# MCU.net
KiCad netlist of a schematic drawn in Altium Designer
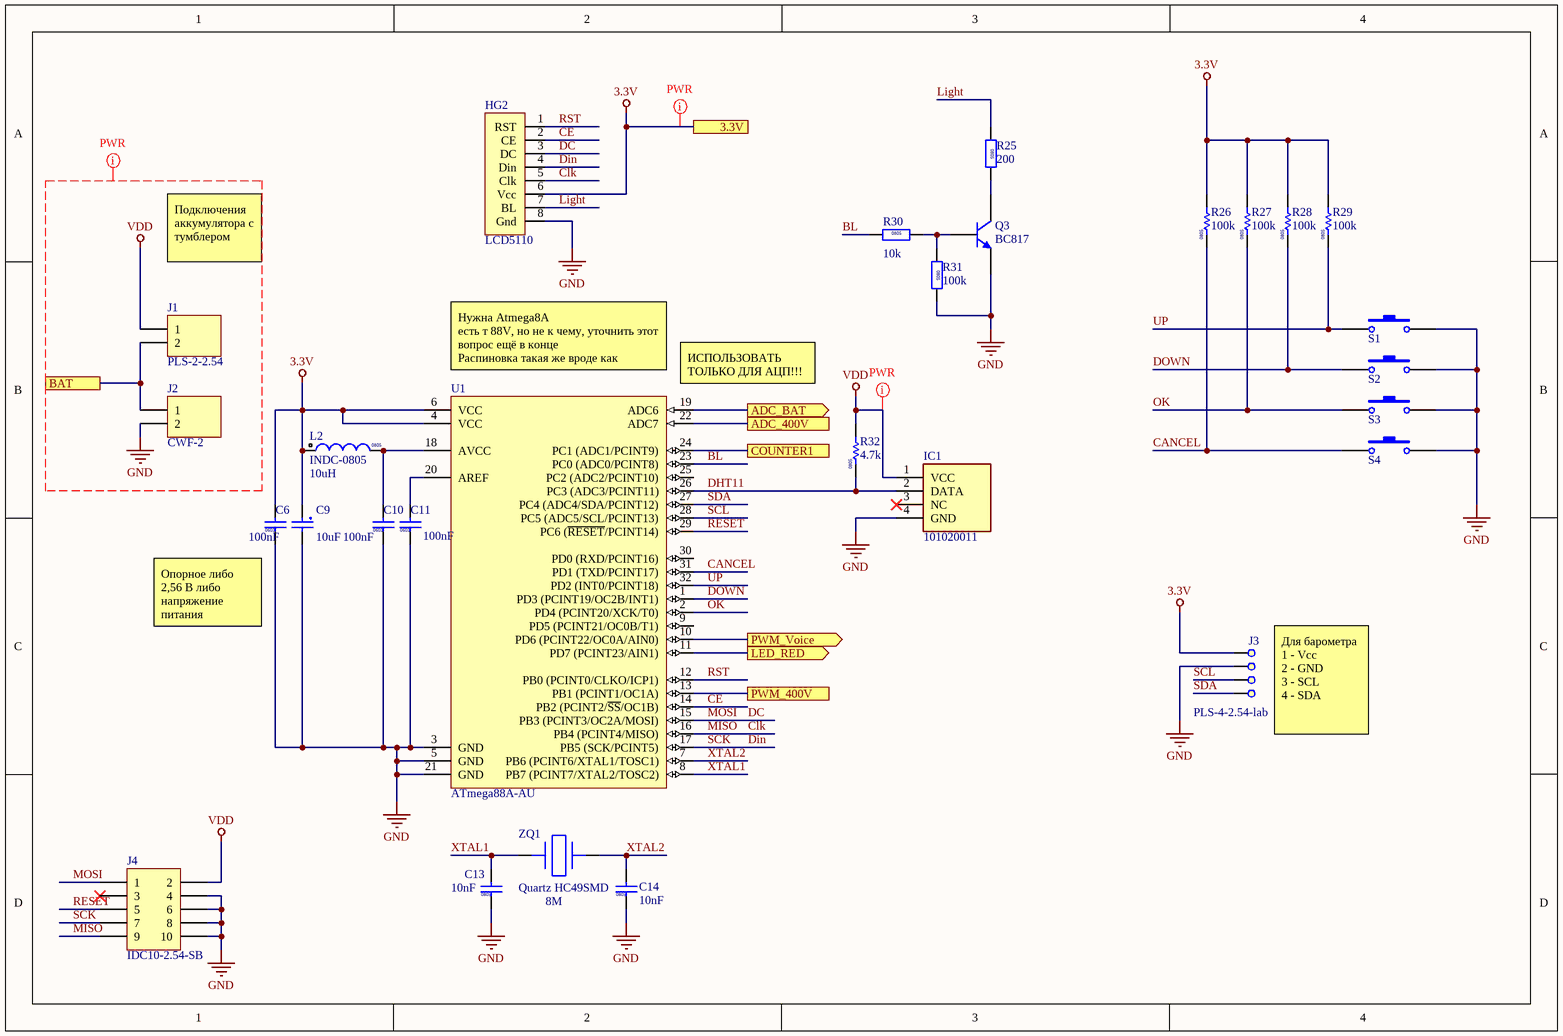
[diagram p0: MCU.SchDoc]

(export (version "E")
  (design (tool "Eeschema 10.0.6"))
  (components
    (comp (ref "C6")
      (value "100nF")
      (footprint "CAPC1608-0603L")
      (description "Capacitor 0603")
      (fields (field (name "Comment") "CAPC_0603"))
      (libsource (lib "Passive") (part "CAPC_0603"))
    )
    (comp (ref "C9")
      (value "10uF")
      (footprint "TCAPC_A")
      (description "Capacitor tantalum SMD type A")
      (fields (field (name "Comment") "TCAPC_A"))
      (libsource (lib "Passive") (part "TCAPC_A"))
    )
    (comp (ref "C10")
      (value "100nF")
      (footprint "CAPC1608-0603L")
      (description "Capacitor 0603")
      (fields (field (name "Comment") "CAPC_0603"))
      (libsource (lib "Passive") (part "CAPC_0603"))
    )
    (comp (ref "C11")
      (value "100nF")
      (footprint "CAPC1608-0603L")
      (description "Capacitor 0603")
      (fields (field (name "Comment") "CAPC_0603"))
      (libsource (lib "Passive") (part "CAPC_0603"))
    )
    (comp (ref "C13")
      (value "10nF")
      (footprint "CAPC2012-0805M")
      (description "Capacitor 0805")
      (fields (field (name "Comment") "CAPC_0805"))
      (libsource (lib "Passive") (part "CAPC_0805"))
    )
    (comp (ref "C14")
      (value "10nF")
      (footprint "CAPC2012-0805M")
      (description "Capacitor 0805")
      (fields (field (name "Comment") "CAPC_0805"))
      (libsource (lib "Passive") (part "CAPC_0805"))
    )
    (comp (ref "HG2")
      (value "LCD5110")
      (footprint "LCD")
      (description "Дисплей Nokia 5110 84x48")
      (libsource (lib "altium-import") (part "root_0_LCD5110_"))
    )
    (comp (ref "IC1")
      (value "101020011")
      (footprint "SamacSys:HDRV4W80P0X254_1X4_1200X500X1550P")
      (description "Integrated Circuit")
      (fields (field (name "MOUSER PART NUMBER") "713-101020011") (field (name "RS PART NUMBER") "1743237"))
      (libsource (lib "*") (part "101020011"))
    )
    (comp (ref "J1")
      (value "PLS-2-2.54")
      (footprint "PLS-2-2.54")
      (fields (field (name "PUBLISHER") "Altium Limited"))
      (libsource (lib "Connectors") (part "PLS-2-2.54"))
    )
    (comp (ref "J2") (value "CWF-2") (footprint "CWF-2") (libsource (lib "Connectors") (part "CWF-2")))
    (comp (ref "J3")
      (value "PLS-4-2.54-lab")
      (footprint "PLS-4-2.54-lab")
      (fields (field (name "PUBLISHER") "Altium Limited"))
      (libsource (lib "Connectors") (part "PLS-4-2.54-lab"))
    )
    (comp (ref "J4")
      (value "IDC10-2.54-SB")
      (footprint "IDC10-2.54-SB")
      (description "IDC10 2.54 mm pitch Straight, plastic Box")
      (fields (field (name "PUBLISHER") "Altium Limited"))
      (libsource (lib "Connectors") (part "IDC10-2.54-SB"))
    )
    (comp (ref "L2")
      (value "INDC-0805")
      (footprint "INDC2012L")
      (description "Chip Inductor, Body Body 2.0x1.2mm")
      (fields (field (name "ALTIUM_VALUE") "10uH"))
      (libsource (lib "Passive") (part "INDC-0805"))
    )
    (comp (ref "Q3")
      (value "BC817")
      (footprint "SOT23-3M")
      (description "BC817 NPN Transistor")
      (libsource (lib "Discrete") (part "BC817"))
    )
    (comp (ref "R25")
      (value "200")
      (footprint "RESC2012-0805M")
      (description "Resistor 0805")
      (fields (field (name "Comment") "RESC_0805_R"))
      (libsource (lib "Passive") (part "RESC_0805_R"))
    )
    (comp (ref "R26")
      (value "100k")
      (footprint "RESC2012-0805M")
      (description "Resistor 0805")
      (fields (field (name "Comment") "RESC_0805"))
      (libsource (lib "Passive") (part "RESC_0805"))
    )
    (comp (ref "R27")
      (value "100k")
      (footprint "RESC2012-0805M")
      (description "Resistor 0805")
      (fields (field (name "Comment") "RESC_0805"))
      (libsource (lib "Passive") (part "RESC_0805"))
    )
    (comp (ref "R28")
      (value "100k")
      (footprint "RESC2012-0805M")
      (description "Resistor 0805")
      (fields (field (name "Comment") "RESC_0805"))
      (libsource (lib "Passive") (part "RESC_0805"))
    )
    (comp (ref "R29")
      (value "100k")
      (footprint "RESC2012-0805M")
      (description "Resistor 0805")
      (fields (field (name "Comment") "RESC_0805"))
      (libsource (lib "Passive") (part "RESC_0805"))
    )
    (comp (ref "R30")
      (value "10k")
      (footprint "RESC2012-0805M")
      (description "Resistor 0805")
      (fields (field (name "Comment") "RESC_0805_R"))
      (libsource (lib "") (part "RESC_0805_R_1"))
    )
    (comp (ref "R31")
      (value "100k")
      (footprint "RESC2012-0805M")
      (description "Resistor 0805")
      (fields (field (name "Comment") "RESC_0805_R"))
      (libsource (lib "Passive") (part "RESC_0805_R"))
    )
    (comp (ref "R32")
      (value "4.7k")
      (footprint "RESC2012-0805M")
      (description "Resistor 0805")
      (fields (field (name "Comment") "RESC_0805"))
      (libsource (lib "Passive") (part "RESC_0805"))
    )
    (comp (ref "S1")
      (value "Switch")
      (footprint "Switch")
      (fields (field (name "PUBLISHER") "Altium Limited"))
      (libsource (lib "Connectors") (part "Switch"))
    )
    (comp (ref "S2")
      (value "Switch")
      (footprint "Switch")
      (fields (field (name "PUBLISHER") "Altium Limited"))
      (libsource (lib "Connectors") (part "Switch"))
    )
    (comp (ref "S3")
      (value "Switch")
      (footprint "Switch")
      (fields (field (name "PUBLISHER") "Altium Limited"))
      (libsource (lib "Connectors") (part "Switch"))
    )
    (comp (ref "S4")
      (value "Switch")
      (footprint "Switch")
      (fields (field (name "PUBLISHER") "Altium Limited"))
      (libsource (lib "Connectors") (part "Switch"))
    )
    (comp (ref "U1")
      (value "ATmega88A-AU")
      (footprint "32A_L")
      (fields (field (name "PUBLISHER") "Altium Limited"))
      (libsource (lib "altium-import") (part "root_0_ATmega88A-AU_"))
    )
    (comp (ref "ZQ1")
      (value "Quartz HC49SMD")
      (footprint "HC-49SMD")
      (fields (field (name "ALTIUM_VALUE") "8M"))
      (libsource (lib "Passive") (part "Quartz HC49SMD"))
    )
  )
  (nets
    (net (code "1") (name "/ADC_400V") (class "Default")
      (node (ref "U1") (pin "22") (pinfunction "ADC7_22") (pintype "input"))
    )
    (net (code "2") (name "/ADC_BAT") (class "Default")
      (node (ref "U1") (pin "19") (pinfunction "ADC6_19") (pintype "input"))
    )
    (net (code "3") (name "/BAT") (class "Default")
      (node (ref "J1") (pin "2") (pinfunction "2_2") (pintype "passive"))
      (node (ref "J2") (pin "1") (pinfunction "1_1") (pintype "passive"))
    )
    (net (code "4") (name "/BL") (class "Default")
      (node (ref "R30") (pin "1") (pinfunction "1_1") (pintype "passive"))
      (node (ref "U1") (pin "23") (pinfunction "PC0_(ADC0/PCINT8)_23") (pintype "bidirectional"))
    )
    (net (code "5") (name "/CANCEL") (class "Default")
      (node (ref "R26") (pin "1") (pinfunction "1_1") (pintype "passive"))
      (node (ref "S4") (pin "1") (pinfunction "1_1") (pintype "passive"))
      (node (ref "U1") (pin "31") (pinfunction "PD1_(TXD/PCINT17)_31") (pintype "bidirectional"))
    )
    (net (code "6") (name "/CE") (class "Default")
      (node (ref "HG2") (pin "2") (pinfunction "CE_2") (pintype "passive"))
      (node (ref "U1") (pin "14") (pinfunction "PB2_(PCINT2/~{SS}/OC1B)_14") (pintype "bidirectional"))
    )
    (net (code "7") (name "/COUNTER1") (class "Default")
      (node (ref "U1") (pin "24") (pinfunction "PC1_(ADC1/PCINT9)_24") (pintype "bidirectional"))
    )
    (net (code "8") (name "/Clk") (class "Default")
      (node (ref "HG2") (pin "5") (pinfunction "Clk_5") (pintype "passive"))
      (node (ref "J4") (pin "9") (pinfunction "9_9") (pintype "passive"))
      (node (ref "U1") (pin "16") (pinfunction "PB4_(PCINT4/MISO)_16") (pintype "bidirectional"))
    )
    (net (code "9") (name "/DC") (class "Default")
      (node (ref "HG2") (pin "3") (pinfunction "DC_3") (pintype "passive"))
      (node (ref "J4") (pin "1") (pinfunction "1_1") (pintype "passive"))
      (node (ref "U1") (pin "15") (pinfunction "PB3_(PCINT3/OC2A/MOSI)_15") (pintype "bidirectional"))
    )
    (net (code "10") (name "/DHT11") (class "Default")
      (node (ref "IC1") (pin "2") (pinfunction "DATA_2") (pintype "passive"))
      (node (ref "R32") (pin "1") (pinfunction "1_1") (pintype "passive"))
      (node (ref "U1") (pin "26") (pinfunction "PC3_(ADC3/PCINT11)_26") (pintype "bidirectional"))
    )
    (net (code "11") (name "/DOWN") (class "Default")
      (node (ref "R28") (pin "1") (pinfunction "1_1") (pintype "passive"))
      (node (ref "S2") (pin "1") (pinfunction "1_1") (pintype "passive"))
      (node (ref "U1") (pin "1") (pinfunction "PD3_(PCINT19/OC2B/INT1)_1") (pintype "bidirectional"))
    )
    (net (code "12") (name "/Din") (class "Default")
      (node (ref "HG2") (pin "4") (pinfunction "Din_4") (pintype "passive"))
      (node (ref "J4") (pin "7") (pinfunction "7_7") (pintype "passive"))
      (node (ref "U1") (pin "17") (pinfunction "PB5_(SCK/PCINT5)_17") (pintype "bidirectional"))
    )
    (net (code "13") (name "/LED_RED") (class "Default")
      (node (ref "U1") (pin "11") (pinfunction "PD7_(PCINT23/AIN1)_11") (pintype "bidirectional"))
    )
    (net (code "14") (name "/Light") (class "Default")
      (node (ref "HG2") (pin "7") (pinfunction "BL_7") (pintype "passive"))
      (node (ref "R25") (pin "1") (pinfunction "1_1") (pintype "passive"))
    )
    (net (code "15") (name "/OK") (class "Default")
      (node (ref "R27") (pin "1") (pinfunction "1_1") (pintype "passive"))
      (node (ref "S3") (pin "1") (pinfunction "1_1") (pintype "passive"))
      (node (ref "U1") (pin "2") (pinfunction "PD4_(PCINT20/XCK/T0)_2") (pintype "bidirectional"))
    )
    (net (code "16") (name "/PWM_400V") (class "Default")
      (node (ref "U1") (pin "13") (pinfunction "PB1_(PCINT1/OC1A)_13") (pintype "bidirectional"))
    )
    (net (code "17") (name "/PWM_Voice") (class "Default")
      (node (ref "U1") (pin "10") (pinfunction "PD6_(PCINT22/OC0A/AIN0)_10") (pintype "bidirectional"))
    )
    (net (code "18") (name "/RESET") (class "Default")
      (node (ref "J4") (pin "5") (pinfunction "5_5") (pintype "passive"))
      (node (ref "U1") (pin "29") (pinfunction "PC6_(~{RESET}/PCINT14)_29") (pintype "bidirectional"))
    )
    (net (code "19") (name "/RST") (class "Default")
      (node (ref "HG2") (pin "1") (pinfunction "RST_1") (pintype "passive"))
      (node (ref "U1") (pin "12") (pinfunction "PB0_(PCINT0/CLKO/ICP1)_12") (pintype "bidirectional"))
    )
    (net (code "20") (name "/SCL") (class "Default")
      (node (ref "J3") (pin "3") (pinfunction "3_3") (pintype "passive"))
      (node (ref "U1") (pin "28") (pinfunction "PC5_(ADC5/SCL/PCINT13)_28") (pintype "bidirectional"))
    )
    (net (code "21") (name "/SDA") (class "Default")
      (node (ref "J3") (pin "4") (pinfunction "4_4") (pintype "passive"))
      (node (ref "U1") (pin "27") (pinfunction "PC4_(ADC4/SDA/PCINT12)_27") (pintype "bidirectional"))
    )
    (net (code "22") (name "/UP") (class "Default")
      (node (ref "R29") (pin "1") (pinfunction "1_1") (pintype "passive"))
      (node (ref "S1") (pin "1") (pinfunction "1_1") (pintype "passive"))
      (node (ref "U1") (pin "32") (pinfunction "PD2_(INT0/PCINT18)_32") (pintype "bidirectional"))
    )
    (net (code "23") (name "/XTAL1") (class "Default")
      (node (ref "C13") (pin "2") (pinfunction "2_2") (pintype "passive"))
      (node (ref "U1") (pin "8") (pinfunction "PB7_(PCINT7/XTAL2/TOSC2)_8") (pintype "bidirectional"))
      (node (ref "ZQ1") (pin "1") (pinfunction "1_1") (pintype "passive"))
    )
    (net (code "24") (name "/XTAL2") (class "Default")
      (node (ref "C14") (pin "2") (pinfunction "2_2") (pintype "passive"))
      (node (ref "U1") (pin "7") (pinfunction "PB6_(PCINT6/XTAL1/TOSC1)_7") (pintype "bidirectional"))
      (node (ref "ZQ1") (pin "2") (pinfunction "2_2") (pintype "passive"))
    )
    (net (code "25") (name "3.3V") (class "Default")
      (node (ref "C6") (pin "2") (pinfunction "2_2") (pintype "passive"))
      (node (ref "C9") (pin "1") (pinfunction "1_1") (pintype "passive"))
      (node (ref "HG2") (pin "6") (pinfunction "Vcc_6") (pintype "passive"))
      (node (ref "J3") (pin "1") (pinfunction "1_1") (pintype "passive"))
      (node (ref "L2") (pin "1") (pinfunction "1_1") (pintype "passive"))
      (node (ref "R26") (pin "2") (pinfunction "2_2") (pintype "passive"))
      (node (ref "R27") (pin "2") (pinfunction "2_2") (pintype "passive"))
      (node (ref "R28") (pin "2") (pinfunction "2_2") (pintype "passive"))
      (node (ref "R29") (pin "2") (pinfunction "2_2") (pintype "passive"))
      (node (ref "U1") (pin "4") (pinfunction "VCC_4") (pintype "power_in"))
      (node (ref "U1") (pin "6") (pinfunction "VCC_6") (pintype "power_in"))
    )
    (net (code "26") (name "GND") (class "Default")
      (node (ref "C10") (pin "1") (pinfunction "1_1") (pintype "passive"))
      (node (ref "C11") (pin "1") (pinfunction "1_1") (pintype "passive"))
      (node (ref "C13") (pin "1") (pinfunction "1_1") (pintype "passive"))
      (node (ref "C14") (pin "1") (pinfunction "1_1") (pintype "passive"))
      (node (ref "C6") (pin "1") (pinfunction "1_1") (pintype "passive"))
      (node (ref "C9") (pin "2") (pinfunction "2_2") (pintype "passive"))
      (node (ref "HG2") (pin "8") (pinfunction "Gnd_8") (pintype "passive"))
      (node (ref "IC1") (pin "4") (pinfunction "GND_4") (pintype "passive"))
      (node (ref "J2") (pin "2") (pinfunction "2_2") (pintype "passive"))
      (node (ref "J3") (pin "2") (pinfunction "2_2") (pintype "passive"))
      (node (ref "J4") (pin "10") (pinfunction "10_10") (pintype "passive"))
      (node (ref "J4") (pin "4") (pinfunction "4_4") (pintype "passive"))
      (node (ref "J4") (pin "6") (pinfunction "6_6") (pintype "passive"))
      (node (ref "J4") (pin "8") (pinfunction "8_8") (pintype "passive"))
      (node (ref "Q3") (pin "2") (pinfunction "E_2") (pintype "passive"))
      (node (ref "R31") (pin "2") (pinfunction "2_2") (pintype "passive"))
      (node (ref "S1") (pin "2") (pinfunction "2_2") (pintype "passive"))
      (node (ref "S2") (pin "2") (pinfunction "2_2") (pintype "passive"))
      (node (ref "S3") (pin "2") (pinfunction "2_2") (pintype "passive"))
      (node (ref "S4") (pin "2") (pinfunction "2_2") (pintype "passive"))
      (node (ref "U1") (pin "21") (pinfunction "GND_21") (pintype "power_in"))
      (node (ref "U1") (pin "3") (pinfunction "GND_3") (pintype "power_in"))
      (node (ref "U1") (pin "5") (pinfunction "GND_5") (pintype "power_in"))
    )
    (net (code "27") (name "Net-(Q3-B)") (class "Default")
      (node (ref "Q3") (pin "1") (pinfunction "B_1") (pintype "passive"))
      (node (ref "R30") (pin "2") (pinfunction "2_2") (pintype "passive"))
      (node (ref "R31") (pin "1") (pinfunction "1_1") (pintype "passive"))
    )
    (net (code "28") (name "Net-(Q3-C)") (class "Default")
      (node (ref "Q3") (pin "3") (pinfunction "C_3") (pintype "passive"))
      (node (ref "R25") (pin "2") (pinfunction "2_2") (pintype "passive"))
    )
    (net (code "29") (name "Net-(U1-AREF)") (class "Default")
      (node (ref "C11") (pin "2") (pinfunction "2_2") (pintype "passive"))
      (node (ref "U1") (pin "20") (pinfunction "AREF_20") (pintype "passive"))
    )
    (net (code "30") (name "Net-(U1-AVCC)") (class "Default")
      (node (ref "C10") (pin "2") (pinfunction "2_2") (pintype "passive"))
      (node (ref "L2") (pin "2") (pinfunction "2_2") (pintype "passive"))
      (node (ref "U1") (pin "18") (pinfunction "AVCC_18") (pintype "power_in"))
    )
    (net (code "31") (name "VDD") (class "Default")
      (node (ref "IC1") (pin "1") (pinfunction "VCC_1") (pintype "passive"))
      (node (ref "J1") (pin "1") (pinfunction "1_1") (pintype "passive"))
      (node (ref "J4") (pin "2") (pinfunction "2_2") (pintype "passive"))
      (node (ref "R32") (pin "2") (pinfunction "2_2") (pintype "passive"))
    )
    (net (code "32") (name "unconnected-(IC1-NC-Pad3)") (class "Default")
      (node (ref "IC1") (pin "3") (pinfunction "NC_3") (pintype "passive+no_connect"))
    )
    (net (code "33") (name "unconnected-(J4-Pad3)") (class "Default")
      (node (ref "J4") (pin "3") (pinfunction "3_3") (pintype "passive+no_connect"))
    )
    (net (code "34") (name "unconnected-(U1-PC2_(ADC2{slash}PCINT10)-Pad25)") (class "Default")
      (node (ref "U1") (pin "25") (pinfunction "PC2_(ADC2/PCINT10)_25") (pintype "bidirectional"))
    )
    (net (code "35") (name "unconnected-(U1-PD0_(RXD{slash}PCINT16)-Pad30)") (class "Default")
      (node (ref "U1") (pin "30") (pinfunction "PD0_(RXD/PCINT16)_30") (pintype "bidirectional"))
    )
    (net (code "36") (name "unconnected-(U1-PD5_(PCINT21{slash}OC0B{slash}T1)-Pad9)") (class "Default")
      (node (ref "U1") (pin "9") (pinfunction "PD5_(PCINT21/OC0B/T1)_9") (pintype "bidirectional"))
    )
  )
)
